# LedDimming.net
KiCad netlist of a schematic drawn in Altium Designer
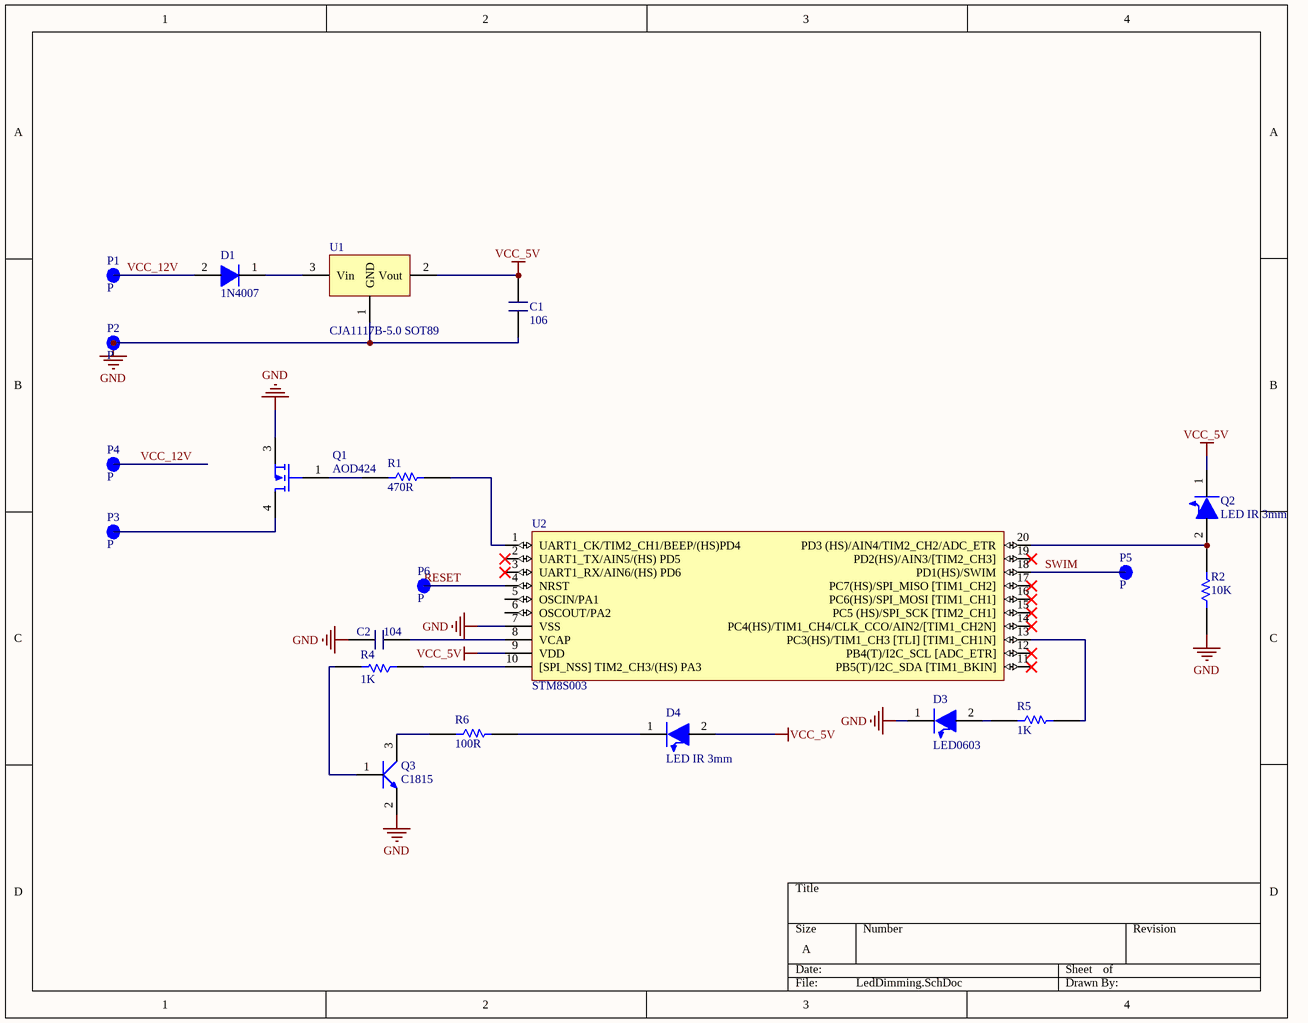
[diagram p0: LedDimming.SchDoc]

(export (version "E")
  (design (tool "Eeschema 10.0.6"))
  (components
    (comp (ref "C1")
      (value "106")
      (footprint "CAPC2012X12N")
      (libsource (lib "Integrated_Library1") (part "Capacitor 106"))
    )
    (comp (ref "C2")
      (value "104")
      (footprint "CAPC2012X12N")
      (libsource (lib "Integrated_Library1") (part "Capacitor 104 0603"))
    )
    (comp (ref "D1")
      (value "1N4007")
      (footprint "SODFL504X244-2N")
      (description "1N4007_SMD")
      (libsource (lib "Integrated_Library1") (part "1N4007_SMD Diode"))
    )
    (comp (ref "D3")
      (value "LED0603")
      (footprint "DIOC1608X06N")
      (libsource (lib "Integrated_Library1") (part "LED0603"))
    )
    (comp (ref "D4")
      (value "LED IR 3mm")
      (footprint "LED_IR_3mm-SMD- Modifire")
      (libsource (lib "Integrated_Library1") (part "LED IR 3mm"))
    )
    (comp (ref "P1") (value "P") (footprint "Point") (libsource (lib "Integrated_Library1") (part "Point")))
    (comp (ref "P2") (value "P") (footprint "Point") (libsource (lib "Integrated_Library1") (part "Point")))
    (comp (ref "P3") (value "P") (footprint "Point") (libsource (lib "Integrated_Library1") (part "Point")))
    (comp (ref "P4") (value "P") (footprint "Point") (libsource (lib "Integrated_Library1") (part "Point")))
    (comp (ref "P5") (value "P") (footprint "Point") (libsource (lib "Integrated_Library1") (part "Point")))
    (comp (ref "P6") (value "P") (footprint "Point") (libsource (lib "Integrated_Library1") (part "Point")))
    (comp (ref "Q1")
      (value "AOD424")
      (footprint "DPAK228P991X229-3N_TO252")
      (description "AOD424 20V N-Channel MOSFET")
      (libsource (lib "Integrated_Library1") (part "AOD424 20V N-Channel MOSFET"))
    )
    (comp (ref "Q2")
      (value "LED IR 3mm")
      (footprint "LED_IR_3mm-SMD- Modifire")
      (libsource (lib "Integrated_Library1") (part "LED IR 3mm"))
    )
    (comp (ref "Q3")
      (value "C1815")
      (footprint "SOT95P278X125-3N")
      (description "SOT-23 Plastic-Encapsulate Transistors")
      (libsource (lib "Integrated_Library1") (part "Transitor C1815 NPN"))
    )
    (comp (ref "R1")
      (value "470R")
      (footprint "RESC2608X06N_0603")
      (description "Thick Film Resistors - SMD 470 ohm 5%")
      (libsource (lib "Integrated_Library1") (part "R470_0603_5%"))
    )
    (comp (ref "R2")
      (value "10K")
      (footprint "RESC2608X06N_0603")
      (description "RES SMD 10K OHM 1% 1/4W 0603")
      (libsource (lib "Integrated_Library1") (part "R10k_0603_5%"))
    )
    (comp (ref "R4")
      (value "1K")
      (footprint "RESC2608X06N_0603")
      (description "Thick Film Resistors - SMD 0603 1kOHMS 5% 1/10WATT")
      (libsource (lib "Integrated_Library1") (part "1k_0603_5%"))
    )
    (comp (ref "R5")
      (value "1K")
      (footprint "RESC2608X06N_0603")
      (description "Thick Film Resistors - SMD 0603 1kOHMS 5% 1/10WATT")
      (libsource (lib "Integrated_Library1") (part "1k_0603_5%"))
    )
    (comp (ref "R6")
      (value "100R")
      (footprint "RESC2608X06N_0603")
      (description "Thick Film Resistors - SMD 0603 100OHMS 5% 1/10WATT")
      (libsource (lib "Integrated_Library1") (part "R100_0603_5%"))
    )
    (comp (ref "U1")
      (value "CJA1117B-5.0 SOT89")
      (footprint "SOT89-150P409X160-3N")
      (description "CJA1117B-5.0 SOT89 Power IC 1A 5V_IC")
      (libsource (lib "Integrated_Library1") (part "CJA1117B-5.0 SOT89"))
    )
    (comp (ref "U2")
      (value "STM8S003")
      (footprint "TSOP65P640X120-20N")
      (description "MCU 8-bit STM8S STM8 CISC 8KB Flash 3.3V/5V 20-Pin TSSOP T/R")
      (libsource (lib "Integrated_Library1") (part "STM8S003"))
    )
  )
  (nets
    (net (code "1") (name "/RESET") (class "Default")
      (node (ref "P6") (pin "1") (pinfunction "1_1") (pintype "passive"))
      (node (ref "U2") (pin "4") (pinfunction "NRST_4") (pintype "bidirectional"))
    )
    (net (code "2") (name "/SWIM") (class "Default")
      (node (ref "P5") (pin "1") (pinfunction "1_1") (pintype "passive"))
      (node (ref "U2") (pin "18") (pinfunction "PD1(HS)/SWIM_18") (pintype "bidirectional"))
    )
    (net (code "3") (name "/VCC_12V") (class "Default")
      (node (ref "D1") (pin "2") (pinfunction "A_2") (pintype "passive"))
      (node (ref "P1") (pin "1") (pinfunction "1_1") (pintype "passive"))
      (node (ref "P4") (pin "1") (pinfunction "1_1") (pintype "passive"))
    )
    (net (code "4") (name "GND") (class "Default")
      (node (ref "C1") (pin "1") (pinfunction "1_1") (pintype "passive"))
      (node (ref "C2") (pin "1") (pinfunction "1_1") (pintype "passive"))
      (node (ref "D3") (pin "1") (pinfunction "A_1") (pintype "passive"))
      (node (ref "P2") (pin "1") (pinfunction "1_1") (pintype "passive"))
      (node (ref "Q1") (pin "3") (pinfunction "S_3") (pintype "passive"))
      (node (ref "Q3") (pin "2") (pinfunction "E_2") (pintype "passive"))
      (node (ref "R2") (pin "1") (pinfunction "1_1") (pintype "passive"))
      (node (ref "U1") (pin "1") (pinfunction "GND_1") (pintype "power_in"))
      (node (ref "U2") (pin "7") (pinfunction "VSS_7") (pintype "power_in"))
    )
    (net (code "5") (name "Net-(D1-C)") (class "Default")
      (node (ref "D1") (pin "1") (pinfunction "C_1") (pintype "passive"))
      (node (ref "U1") (pin "3") (pinfunction "Vin_3") (pintype "power_in"))
    )
    (net (code "6") (name "Net-(D3-C)") (class "Default")
      (node (ref "D3") (pin "2") (pinfunction "C_2") (pintype "passive"))
      (node (ref "R5") (pin "1") (pinfunction "1_1") (pintype "passive"))
    )
    (net (code "7") (name "Net-(D4-A)") (class "Default")
      (node (ref "D4") (pin "1") (pinfunction "A_1") (pintype "passive"))
      (node (ref "R6") (pin "2") (pinfunction "2_2") (pintype "passive"))
    )
    (net (code "8") (name "Net-(Q1-D)") (class "Default")
      (node (ref "P3") (pin "1") (pinfunction "1_1") (pintype "passive"))
      (node (ref "Q1") (pin "4") (pinfunction "D_4") (pintype "passive"))
    )
    (net (code "9") (name "Net-(Q1-G)") (class "Default")
      (node (ref "Q1") (pin "1") (pinfunction "G_1") (pintype "passive"))
      (node (ref "R1") (pin "1") (pinfunction "1_1") (pintype "passive"))
    )
    (net (code "10") (name "Net-(Q2-C)") (class "Default")
      (node (ref "Q2") (pin "2") (pinfunction "C_2") (pintype "passive"))
      (node (ref "R2") (pin "2") (pinfunction "2_2") (pintype "passive"))
      (node (ref "U2") (pin "20") (pinfunction "PD3_(HS)/AIN4/TIM2_CH2/ADC_ETR_20") (pintype "bidirectional"))
    )
    (net (code "11") (name "Net-(Q3-B)") (class "Default")
      (node (ref "Q3") (pin "1") (pinfunction "B_1") (pintype "passive"))
      (node (ref "R4") (pin "2") (pinfunction "2_2") (pintype "passive"))
    )
    (net (code "12") (name "Net-(Q3-C)") (class "Default")
      (node (ref "Q3") (pin "3") (pinfunction "C_3") (pintype "passive"))
      (node (ref "R6") (pin "1") (pinfunction "1_1") (pintype "passive"))
    )
    (net (code "13") (name "Net-(U2-PC3(HS){slash}TIM1_CH3_[TLI]_[TIM1_CH1N])") (class "Default")
      (node (ref "R5") (pin "2") (pinfunction "2_2") (pintype "passive"))
      (node (ref "U2") (pin "13") (pinfunction "PC3(HS)/TIM1_CH3_[TLI]_[TIM1_CH1N]_13") (pintype "bidirectional"))
    )
    (net (code "14") (name "Net-(U2-UART1_CK{slash}TIM2_CH1{slash}BEEP{slash}(HS)PD4)") (class "Default")
      (node (ref "R1") (pin "2") (pinfunction "2_2") (pintype "passive"))
      (node (ref "U2") (pin "1") (pinfunction "UART1_CK/TIM2_CH1/BEEP/(HS)PD4_1") (pintype "bidirectional"))
    )
    (net (code "15") (name "Net-(U2-VCAP)") (class "Default")
      (node (ref "C2") (pin "2") (pinfunction "2_2") (pintype "passive"))
      (node (ref "U2") (pin "8") (pinfunction "VCAP_8") (pintype "power_in"))
    )
    (net (code "16") (name "Net-(U2-[SPI_NSS]_TIM2_CH3{slash}(HS)_PA3)") (class "Default")
      (node (ref "R4") (pin "1") (pinfunction "1_1") (pintype "passive"))
      (node (ref "U2") (pin "10") (pinfunction "[SPI_NSS]_TIM2_CH3/(HS)_PA3_10") (pintype "power_in"))
    )
    (net (code "17") (name "VCC_5V") (class "Default")
      (node (ref "C1") (pin "2") (pinfunction "2_2") (pintype "passive"))
      (node (ref "D4") (pin "2") (pinfunction "C_2") (pintype "passive"))
      (node (ref "Q2") (pin "1") (pinfunction "A_1") (pintype "passive"))
      (node (ref "U1") (pin "2") (pinfunction "Vout_2") (pintype "power_in"))
      (node (ref "U2") (pin "9") (pinfunction "VDD_9") (pintype "power_in"))
    )
    (net (code "18") (name "unconnected-(U2-OSCIN{slash}PA1-Pad5)") (class "Default")
      (node (ref "U2") (pin "5") (pinfunction "OSCIN/PA1_5") (pintype "bidirectional"))
    )
    (net (code "19") (name "unconnected-(U2-OSCOUT{slash}PA2-Pad6)") (class "Default")
      (node (ref "U2") (pin "6") (pinfunction "OSCOUT/PA2_6") (pintype "bidirectional"))
    )
    (net (code "20") (name "unconnected-(U2-PB4(T){slash}I2C_SCL_[ADC_ETR]-Pad12)") (class "Default")
      (node (ref "U2") (pin "12") (pinfunction "PB4(T)/I2C_SCL_[ADC_ETR]_12") (pintype "bidirectional+no_connect"))
    )
    (net (code "21") (name "unconnected-(U2-PB5(T){slash}I2C_SDA_[TIM1_BKIN]-Pad11)") (class "Default")
      (node (ref "U2") (pin "11") (pinfunction "PB5(T)/I2C_SDA_[TIM1_BKIN]_11") (pintype "bidirectional+no_connect"))
    )
    (net (code "22") (name "unconnected-(U2-PC4(HS){slash}TIM1_CH4{slash}CLK_CCO{slash}AIN2{slash}[TIM1_CH2N]-Pad14)") (class "Default")
      (node (ref "U2") (pin "14") (pinfunction "PC4(HS)/TIM1_CH4/CLK_CCO/AIN2/[TIM1_CH2N]_14") (pintype "bidirectional+no_connect"))
    )
    (net (code "23") (name "unconnected-(U2-PC5_(HS){slash}SPI_SCK_[TIM2_CH1]-Pad15)") (class "Default")
      (node (ref "U2") (pin "15") (pinfunction "PC5_(HS)/SPI_SCK_[TIM2_CH1]_15") (pintype "bidirectional+no_connect"))
    )
    (net (code "24") (name "unconnected-(U2-PC6(HS){slash}SPI_MOSI_[TIM1_CH1]-Pad16)") (class "Default")
      (node (ref "U2") (pin "16") (pinfunction "PC6(HS)/SPI_MOSI_[TIM1_CH1]_16") (pintype "bidirectional+no_connect"))
    )
    (net (code "25") (name "unconnected-(U2-PC7(HS){slash}SPI_MISO_[TIM1_CH2]-Pad17)") (class "Default")
      (node (ref "U2") (pin "17") (pinfunction "PC7(HS)/SPI_MISO_[TIM1_CH2]_17") (pintype "bidirectional+no_connect"))
    )
    (net (code "26") (name "unconnected-(U2-PD2(HS){slash}AIN3{slash}[TIM2_CH3]-Pad19)") (class "Default")
      (node (ref "U2") (pin "19") (pinfunction "PD2(HS)/AIN3/[TIM2_CH3]_19") (pintype "bidirectional+no_connect"))
    )
    (net (code "27") (name "unconnected-(U2-UART1_RX{slash}AIN6{slash}(HS)_PD6-Pad3)") (class "Default")
      (node (ref "U2") (pin "3") (pinfunction "UART1_RX/AIN6/(HS)_PD6_3") (pintype "bidirectional+no_connect"))
    )
    (net (code "28") (name "unconnected-(U2-UART1_TX{slash}AIN5{slash}(HS)_PD5-Pad2)") (class "Default")
      (node (ref "U2") (pin "2") (pinfunction "UART1_TX/AIN5/(HS)_PD5_2") (pintype "bidirectional+no_connect"))
    )
  )
)
